# schematic.net
KiCad netlist of a schematic drawn in EAGLE
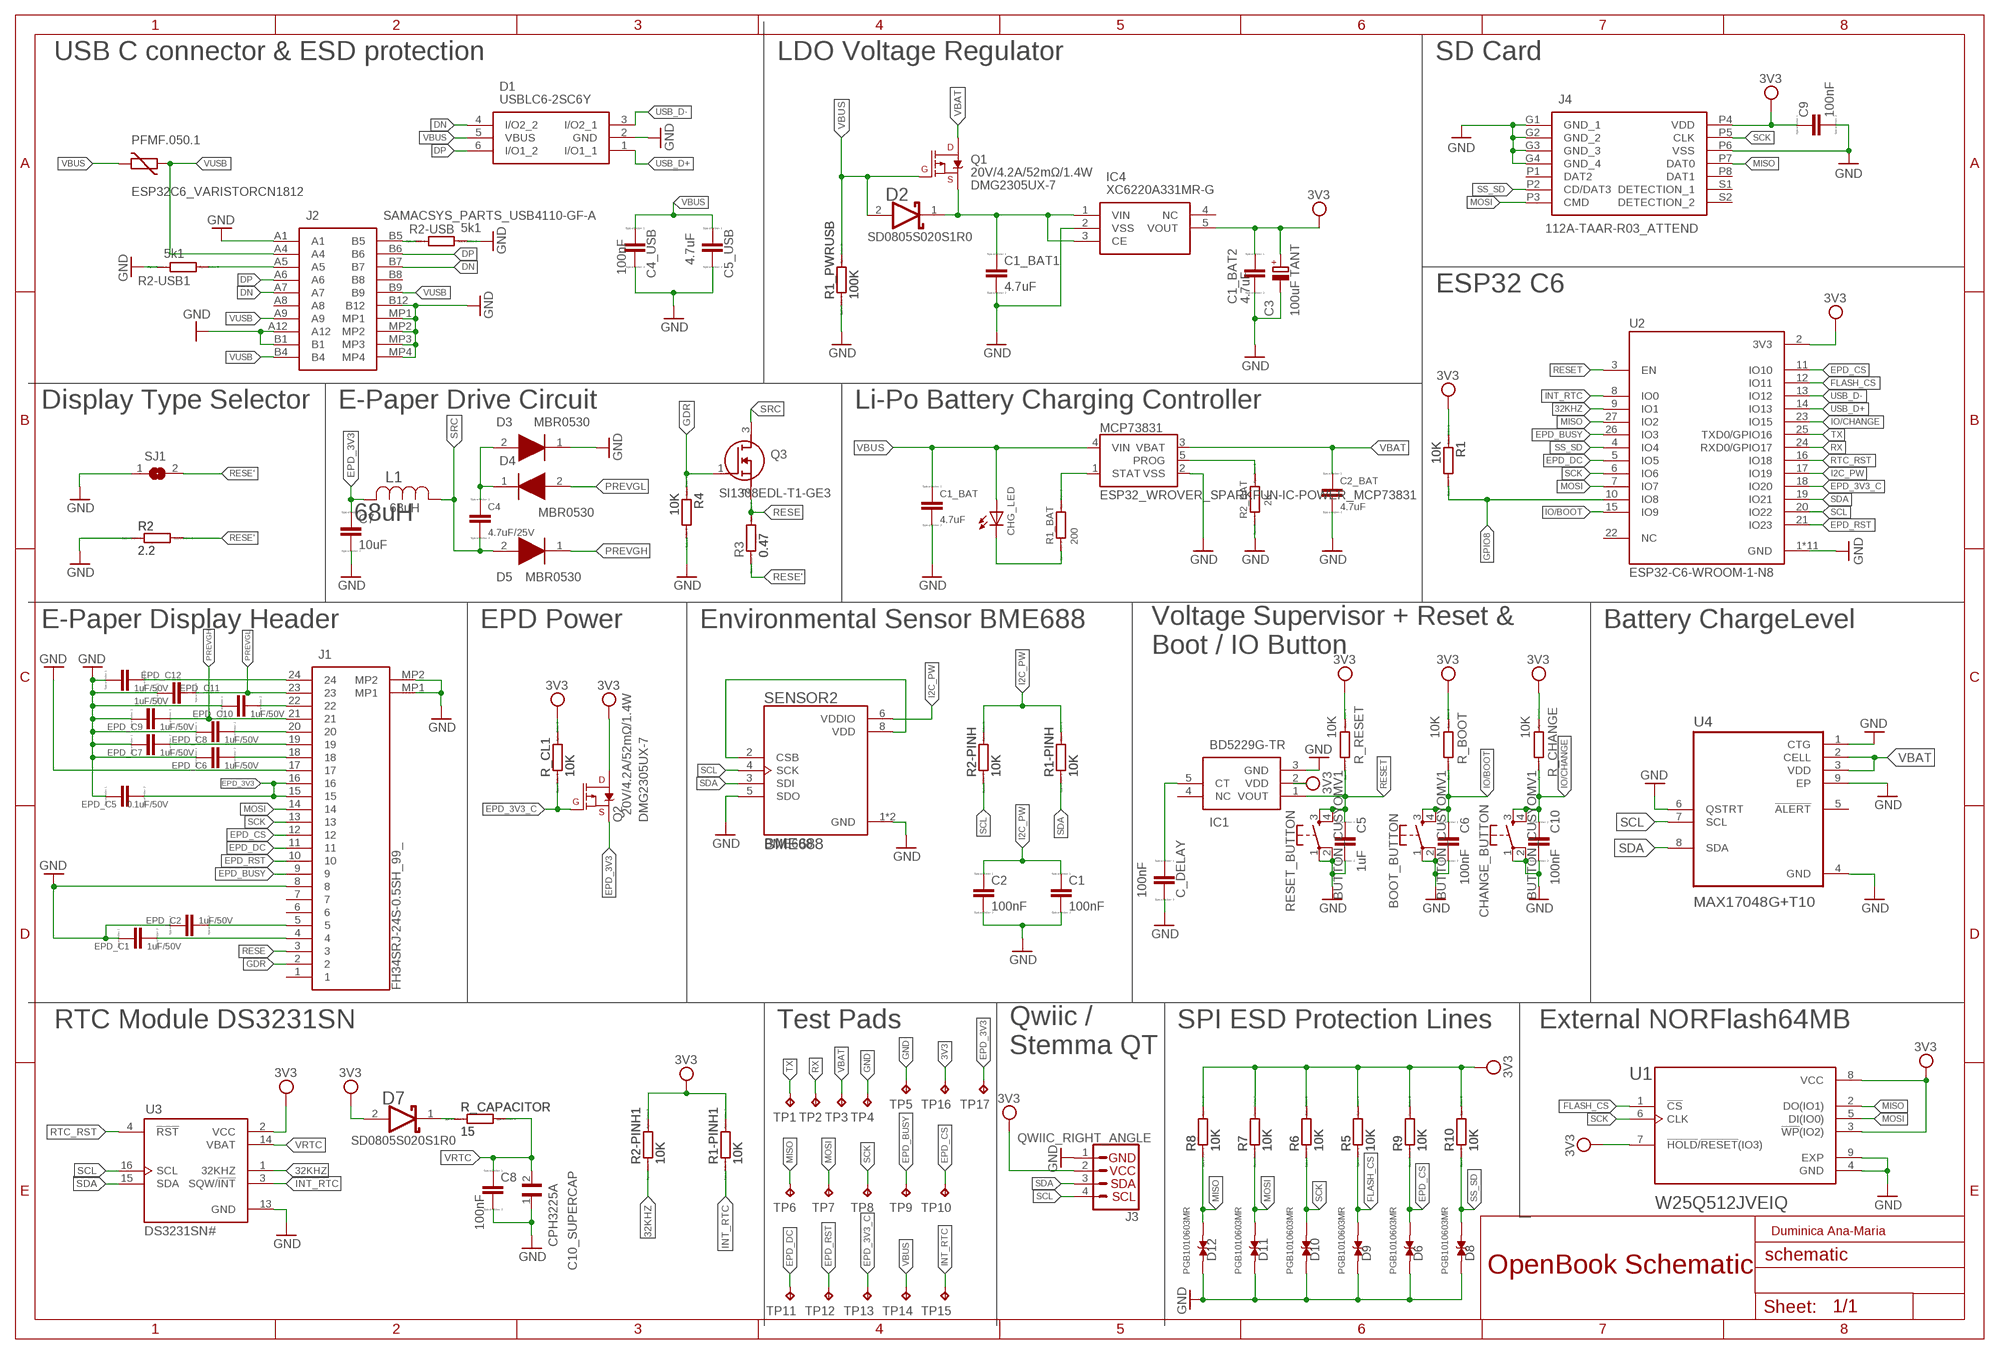
[diagram p0: schematic, sheet 1]

(export (version "E")
  (design (tool "Eeschema 10.0.6"))
  (components
    (comp (ref "BOOT_BUTTON")
      (value "BUTTON_CUSYOMV1")
      (footprint "eagle-import:MYBUTTON")
      (libsource (lib "eagle-import") (part "BUTTON_CUSYOMV1"))
    )
    (comp (ref "C1")
      (value "100nF")
      (footprint "eagle-import:ESP32_WROVER_EAGLE-LTSPICE_C0402")
      (libsource (lib "eagle-import") (part "ESP32_WROVER_EAGLE-LTSPICE_CC0402"))
    )
    (comp (ref "C1_BAT")
      (value "4.7uF")
      (footprint "eagle-import:ESP32_WROVER_EAGLE-LTSPICE_C0402")
      (libsource (lib "eagle-import") (part "ESP32_WROVER_EAGLE-LTSPICE_CC0402"))
    )
    (comp (ref "C1_BAT1")
      (value "4.7uF")
      (footprint "eagle-import:EAGLE-LTSPICE_C0402")
      (libsource (lib "eagle-import") (part "EAGLE-LTSPICE_CC0402"))
    )
    (comp (ref "C1_BAT2")
      (value "4.7uF")
      (footprint "eagle-import:EAGLE-LTSPICE_C0402")
      (libsource (lib "eagle-import") (part "EAGLE-LTSPICE_CC0402"))
    )
    (comp (ref "C2")
      (value "100nF")
      (footprint "eagle-import:ESP32_WROVER_EAGLE-LTSPICE_C0402")
      (libsource (lib "eagle-import") (part "ESP32_WROVER_EAGLE-LTSPICE_CC0402"))
    )
    (comp (ref "C2_BAT")
      (value "4.7uF")
      (footprint "eagle-import:ESP32_WROVER_EAGLE-LTSPICE_C0402")
      (libsource (lib "eagle-import") (part "ESP32_WROVER_EAGLE-LTSPICE_CC0402"))
    )
    (comp (ref "C3")
      (value "100uF TANT")
      (footprint "eagle-import:RCL_CT3528")
      (libsource (lib "eagle-import") (part "RCL_CPOL-EUCT3528"))
    )
    (comp (ref "C4")
      (value "4.7uF/25V")
      (footprint "eagle-import:EAGLE-LTSPICE_C0402")
      (libsource (lib "eagle-import") (part "EAGLE-LTSPICE_CC0402"))
    )
    (comp (ref "C4_USB")
      (value "100nF")
      (footprint "eagle-import:EAGLE-LTSPICE_C0402")
      (libsource (lib "eagle-import") (part "EAGLE-LTSPICE_CC0402"))
    )
    (comp (ref "C5")
      (value "1uF")
      (footprint "eagle-import:ESP32_WROVER_EAGLE-LTSPICE_C0402")
      (libsource (lib "eagle-import") (part "ESP32_WROVER_EAGLE-LTSPICE_CC0402"))
    )
    (comp (ref "C5_USB")
      (value "4.7uF")
      (footprint "eagle-import:EAGLE-LTSPICE_C0402")
      (libsource (lib "eagle-import") (part "EAGLE-LTSPICE_CC0402"))
    )
    (comp (ref "C6")
      (value "100nF")
      (footprint "eagle-import:ESP32_WROVER_EAGLE-LTSPICE_C0402")
      (libsource (lib "eagle-import") (part "ESP32_WROVER_EAGLE-LTSPICE_CC0402"))
    )
    (comp (ref "C7")
      (value "10uF")
      (footprint "eagle-import:EAGLE-LTSPICE_C0402")
      (libsource (lib "eagle-import") (part "EAGLE-LTSPICE_CC0402"))
    )
    (comp (ref "C8")
      (value "100nF")
      (footprint "eagle-import:EAGLE-LTSPICE_C0402")
      (libsource (lib "eagle-import") (part "EAGLE-LTSPICE_CC0402"))
    )
    (comp (ref "C9")
      (value "100nF")
      (footprint "eagle-import:EAGLE-LTSPICE_C0402")
      (libsource (lib "eagle-import") (part "EAGLE-LTSPICE_CC0402"))
    )
    (comp (ref "C10")
      (value "100nF")
      (footprint "eagle-import:ESP32_WROVER_EAGLE-LTSPICE_C0402")
      (libsource (lib "eagle-import") (part "ESP32_WROVER_EAGLE-LTSPICE_CC0402"))
    )
    (comp (ref "C10_SUPERCAP")
      (value "CPH3225A")
      (footprint "eagle-import:CAPCP3225X100N")
      (fields (field (name "MF") "Seiko Instruments"))
      (libsource (lib "eagle-import") (part "CPH3225A"))
    )
    (comp (ref "CHANGE_BUTTON")
      (value "BUTTON_CUSYOMV1")
      (footprint "eagle-import:MYBUTTON")
      (libsource (lib "eagle-import") (part "BUTTON_CUSYOMV1"))
    )
    (comp (ref "CHG_LED")
      (value "ADAFRUIT_LEDCHIP-LED0603")
      (footprint "eagle-import:ADAFRUIT_CHIP-LED0603")
      (libsource (lib "eagle-import") (part "ADAFRUIT_LEDCHIP-LED0603"))
    )
    (comp (ref "C_DELAY")
      (value "100nF")
      (footprint "eagle-import:ESP32_WROVER_EAGLE-LTSPICE_C0402")
      (libsource (lib "eagle-import") (part "ESP32_WROVER_EAGLE-LTSPICE_CC0402"))
    )
    (comp (ref "D1")
      (value "USBLC6-2SC6Y")
      (footprint "eagle-import:SOT95P280X145-6N")
      (fields (field (name "MF") "STMicroelectronics"))
      (libsource (lib "eagle-import") (part "USBLC6-2SC6Y"))
    )
    (comp (ref "D2")
      (value "SD0805S020S1R0")
      (footprint "eagle-import:ESP32_WROVER_AVX---SD0805S020S1R0_AVX_SD0805S020S1R0_0")
      (fields
        (field (name "DIGIKEY_PART_NUMBER") "478-7800-1-ND")
        (field (name "MF") "AVX")
        (field (name "MOUSER_PART_NUMBER") "581-SD0805S020S1R0")
      )
      (libsource (lib "eagle-import") (part "ESP32_WROVER_AVX---SD0805S020S1R0_AVX_SD0805S020S1R0_0_0AVX_SD0805S020S1R0_0_0"))
    )
    (comp (ref "D3")
      (value "MBR0530")
      (footprint "eagle-import:SOD3716X135N")
      (fields (field (name "MF") "ON Semiconductor"))
      (libsource (lib "eagle-import") (part "MBR0530"))
    )
    (comp (ref "D4")
      (value "MBR0530")
      (footprint "eagle-import:SOD3716X135N")
      (fields (field (name "MF") "ON Semiconductor"))
      (libsource (lib "eagle-import") (part "MBR0530"))
    )
    (comp (ref "D5")
      (value "MBR0530")
      (footprint "eagle-import:SOD3716X135N")
      (fields (field (name "MF") "ON Semiconductor"))
      (libsource (lib "eagle-import") (part "MBR0530"))
    )
    (comp (ref "D6")
      (value "PGB1010603MR")
      (footprint "eagle-import:DIOC1608X36N")
      (fields (field (name "MF") "Littelfuse Inc."))
      (libsource (lib "eagle-import") (part "PGB1010603MR"))
    )
    (comp (ref "D7")
      (value "SD0805S020S1R0")
      (footprint "eagle-import:ESP32_WROVER_AVX---SD0805S020S1R0_AVX_SD0805S020S1R0_0")
      (fields
        (field (name "DIGIKEY_PART_NUMBER") "478-7800-1-ND")
        (field (name "MF") "AVX")
        (field (name "MOUSER_PART_NUMBER") "581-SD0805S020S1R0")
      )
      (libsource (lib "eagle-import") (part "ESP32_WROVER_AVX---SD0805S020S1R0_AVX_SD0805S020S1R0_0_0AVX_SD0805S020S1R0_0_0"))
    )
    (comp (ref "D8")
      (value "PGB1010603MR")
      (footprint "eagle-import:DIOC1608X36N")
      (fields (field (name "MF") "Littelfuse Inc."))
      (libsource (lib "eagle-import") (part "PGB1010603MR"))
    )
    (comp (ref "D9")
      (value "PGB1010603MR")
      (footprint "eagle-import:DIOC1608X36N")
      (fields (field (name "MF") "Littelfuse Inc."))
      (libsource (lib "eagle-import") (part "PGB1010603MR"))
    )
    (comp (ref "D10")
      (value "PGB1010603MR")
      (footprint "eagle-import:DIOC1608X36N")
      (fields (field (name "MF") "Littelfuse Inc."))
      (libsource (lib "eagle-import") (part "PGB1010603MR"))
    )
    (comp (ref "D11")
      (value "PGB1010603MR")
      (footprint "eagle-import:DIOC1608X36N")
      (fields (field (name "MF") "Littelfuse Inc."))
      (libsource (lib "eagle-import") (part "PGB1010603MR"))
    )
    (comp (ref "D12")
      (value "PGB1010603MR")
      (footprint "eagle-import:DIOC1608X36N")
      (fields (field (name "MF") "Littelfuse Inc."))
      (libsource (lib "eagle-import") (part "PGB1010603MR"))
    )
    (comp (ref "EPD_C1")
      (value "1uF/50V")
      (footprint "eagle-import:ESP32_WROVER_EAGLE-LTSPICE_C0402")
      (libsource (lib "eagle-import") (part "ESP32_WROVER_EAGLE-LTSPICE_CC0402"))
    )
    (comp (ref "EPD_C2")
      (value "1uF/50V")
      (footprint "eagle-import:ESP32_WROVER_EAGLE-LTSPICE_C0402")
      (libsource (lib "eagle-import") (part "ESP32_WROVER_EAGLE-LTSPICE_CC0402"))
    )
    (comp (ref "EPD_C5")
      (value "0.1uF/50V")
      (footprint "eagle-import:ESP32_WROVER_EAGLE-LTSPICE_C0402")
      (libsource (lib "eagle-import") (part "ESP32_WROVER_EAGLE-LTSPICE_CC0402"))
    )
    (comp (ref "EPD_C6")
      (value "1uF/50V")
      (footprint "eagle-import:ESP32_WROVER_EAGLE-LTSPICE_C0402")
      (libsource (lib "eagle-import") (part "ESP32_WROVER_EAGLE-LTSPICE_CC0402"))
    )
    (comp (ref "EPD_C7")
      (value "1uF/50V")
      (footprint "eagle-import:ESP32_WROVER_EAGLE-LTSPICE_C0402")
      (libsource (lib "eagle-import") (part "ESP32_WROVER_EAGLE-LTSPICE_CC0402"))
    )
    (comp (ref "EPD_C8")
      (value "1uF/50V")
      (footprint "eagle-import:ESP32_WROVER_EAGLE-LTSPICE_C0402")
      (libsource (lib "eagle-import") (part "ESP32_WROVER_EAGLE-LTSPICE_CC0402"))
    )
    (comp (ref "EPD_C9")
      (value "1uF/50V")
      (footprint "eagle-import:ESP32_WROVER_EAGLE-LTSPICE_C0402")
      (libsource (lib "eagle-import") (part "ESP32_WROVER_EAGLE-LTSPICE_CC0402"))
    )
    (comp (ref "EPD_C10")
      (value "1uF/50V")
      (footprint "eagle-import:ESP32_WROVER_EAGLE-LTSPICE_C0402")
      (libsource (lib "eagle-import") (part "ESP32_WROVER_EAGLE-LTSPICE_CC0402"))
    )
    (comp (ref "EPD_C11")
      (value "1uF/50V")
      (footprint "eagle-import:ESP32_WROVER_EAGLE-LTSPICE_C0402")
      (libsource (lib "eagle-import") (part "ESP32_WROVER_EAGLE-LTSPICE_CC0402"))
    )
    (comp (ref "EPD_C12")
      (value "1uF/50V")
      (footprint "eagle-import:ESP32_WROVER_EAGLE-LTSPICE_C0402")
      (libsource (lib "eagle-import") (part "ESP32_WROVER_EAGLE-LTSPICE_CC0402"))
    )
    (comp (ref "IC1")
      (value "BD5229G-TR")
      (footprint "eagle-import:SOT95P280X125-5N")
      (fields (field (name "MOUSER_PART_NUMBER") "755-BD5229G-TR"))
      (libsource (lib "eagle-import") (part "BD5229G-TR"))
    )
    (comp (ref "IC4")
      (value "XC6220A331MR-G")
      (footprint "eagle-import:SOT95P280X120-5N")
      (fields (field (name "MOUSER_PART_NUMBER") "865-XC6220A331MR-G"))
      (libsource (lib "eagle-import") (part "XC6220A331MR-G"))
    )
    (comp (ref "J1")
      (value "FH34SRJ-24S-0.5SH_99_")
      (footprint "eagle-import:FH34SRJ24S05SH99")
      (fields
        (field (name "MANUFACTURER_PART_NUMBER") "FH34SRJ-24S-0.5SH(99)")
        (field (name "MOUSER_PART_NUMBER") "798-FH34SRJ24S05SH99")
      )
      (libsource (lib "eagle-import") (part "FH34SRJ-24S-0.5SH_99_"))
    )
    (comp (ref "J2")
      (value "SAMACSYS_PARTS_USB4110-GF-A")
      (footprint "eagle-import:SAMACSYS_PARTS_USB4110GFA")
      (fields
        (field (name "MANUFACTURER_PART_NUMBER") "USB4110-GF-A")
        (field (name "MOUSER_PART_NUMBER") "640-USB4110-GF-A")
      )
      (libsource (lib "eagle-import") (part "SAMACSYS_PARTS_USB4110-GF-A"))
    )
    (comp (ref "J3")
      (value "QWIIC_RIGHT_ANGLE")
      (footprint "eagle-import:JST04_1MM_RA")
      (libsource (lib "eagle-import") (part "QWIIC_CONNECTORJS-1MM"))
    )
    (comp (ref "J4")
      (value "112A-TAAR-R03_ATTEND")
      (footprint "eagle-import:112ATAARR03ATTEND")
      (fields (field (name "MANUFACTURER_PART_NUMBER") "112A-TAAR-R03 ATTEND"))
      (libsource (lib "eagle-import") (part "112A-TAAR-R03_ATTEND"))
    )
    (comp (ref "L1")
      (value "68uH")
      (footprint "eagle-import:IND_4828-WE-TPC_WRE")
      (fields
        (field (name "MANUFACTURER_PART_NUMBER") "744043680")
        (field (name "COPYRIGHT") "Copyright (C) 2024 Ultra Librarian. All rights reserved.")
      )
      (libsource (lib "eagle-import") (part "744043680IND_4828-WE-TPC_WRE"))
    )
    (comp (ref "MCP73831")
      (value "ESP32_WROVER_SPARKFUN-IC-POWER_MCP73831")
      (footprint "eagle-import:ESP32_WROVER_SPARKFUN-IC-POWER_SOT23-5")
      (libsource (lib "eagle-import") (part "ESP32_WROVER_SPARKFUN-IC-POWER_MCP73831"))
    )
    (comp (ref "PFMF.050.1")
      (value "ESP32C6_VARISTORCN1812")
      (footprint "eagle-import:ESP32C6_VARISTOR_CT_CN1812")
      (libsource (lib "eagle-import") (part "ESP32C6_VARISTORCN1812"))
    )
    (comp (ref "Q1")
      (value "20V/4.2A/52mΩ/1.4W")
      (footprint "eagle-import:ESP32_WROVER_SPARKFUN-DISCRETESEMI_SOT23-3")
      (libsource (lib "eagle-import") (part "ESP32_WROVER_SPARKFUN-DISCRETESEMI_MOSFET_PCH-DMG2305UX-7"))
    )
    (comp (ref "Q2")
      (value "20V/4.2A/52mΩ/1.4W")
      (footprint "eagle-import:ESP32_WROVER_SPARKFUN-DISCRETESEMI_SOT23-3")
      (libsource (lib "eagle-import") (part "ESP32_WROVER_SPARKFUN-DISCRETESEMI_MOSFET_PCH-DMG2305UX-7"))
    )
    (comp (ref "Q3")
      (value "SI1308EDL-T1-GE3")
      (footprint "eagle-import:SOT65P210X110-3N")
      (fields (field (name "MF") "Vishay Siliconix"))
      (libsource (lib "eagle-import") (part "SI1308EDL-T1-GE3"))
    )
    (comp (ref "R1")
      (value "10K")
      (footprint "eagle-import:ESP32_WROVER_EAGLE-LTSPICE_R0402")
      (libsource (lib "eagle-import") (part "ESP32_WROVER_EAGLE-LTSPICE_RR0402"))
    )
    (comp (ref "R1-PINH")
      (value "10K")
      (footprint "eagle-import:ESP32_WROVER_EAGLE-LTSPICE_R0402")
      (libsource (lib "eagle-import") (part "ESP32_WROVER_EAGLE-LTSPICE_RR0402"))
    )
    (comp (ref "R1-PINH1")
      (value "10K")
      (footprint "eagle-import:ESP32_WROVER_EAGLE-LTSPICE_R0402")
      (libsource (lib "eagle-import") (part "ESP32_WROVER_EAGLE-LTSPICE_RR0402"))
    )
    (comp (ref "R1_BAT")
      (value "200")
      (footprint "eagle-import:ESP32_WROVER_EAGLE-LTSPICE_R0402")
      (libsource (lib "eagle-import") (part "ESP32_WROVER_EAGLE-LTSPICE_RR0402"))
    )
    (comp (ref "R1_PWRUSB")
      (value "100K")
      (footprint "eagle-import:ESP32_WROVER_EAGLE-LTSPICE_R0402")
      (libsource (lib "eagle-import") (part "ESP32_WROVER_EAGLE-LTSPICE_RR0402"))
    )
    (comp (ref "R2")
      (value "2.2")
      (footprint "eagle-import:ESP32_WROVER_EAGLE-LTSPICE_R0402")
      (libsource (lib "eagle-import") (part "ESP32_WROVER_EAGLE-LTSPICE_RR0402"))
    )
    (comp (ref "R2-PINH")
      (value "10K")
      (footprint "eagle-import:ESP32_WROVER_EAGLE-LTSPICE_R0402")
      (libsource (lib "eagle-import") (part "ESP32_WROVER_EAGLE-LTSPICE_RR0402"))
    )
    (comp (ref "R2-PINH1")
      (value "10K")
      (footprint "eagle-import:ESP32_WROVER_EAGLE-LTSPICE_R0402")
      (libsource (lib "eagle-import") (part "ESP32_WROVER_EAGLE-LTSPICE_RR0402"))
    )
    (comp (ref "R2-USB")
      (value "5k1")
      (footprint "eagle-import:ESP32_WROVER_EAGLE-LTSPICE_R0402")
      (libsource (lib "eagle-import") (part "ESP32_WROVER_EAGLE-LTSPICE_RR0402"))
    )
    (comp (ref "R2-USB1")
      (value "5k1")
      (footprint "eagle-import:ESP32_WROVER_EAGLE-LTSPICE_R0402")
      (libsource (lib "eagle-import") (part "ESP32_WROVER_EAGLE-LTSPICE_RR0402"))
    )
    (comp (ref "R2_BAT")
      (value "2K")
      (footprint "eagle-import:ESP32_WROVER_EAGLE-LTSPICE_R0402")
      (libsource (lib "eagle-import") (part "ESP32_WROVER_EAGLE-LTSPICE_RR0402"))
    )
    (comp (ref "R3")
      (value "0.47")
      (footprint "eagle-import:ESP32_WROVER_EAGLE-LTSPICE_R0402")
      (libsource (lib "eagle-import") (part "ESP32_WROVER_EAGLE-LTSPICE_RR0402"))
    )
    (comp (ref "R4")
      (value "10K")
      (footprint "eagle-import:ESP32_WROVER_EAGLE-LTSPICE_R0402")
      (libsource (lib "eagle-import") (part "ESP32_WROVER_EAGLE-LTSPICE_RR0402"))
    )
    (comp (ref "R5")
      (value "10K")
      (footprint "eagle-import:ESP32_WROVER_EAGLE-LTSPICE_R0402")
      (libsource (lib "eagle-import") (part "ESP32_WROVER_EAGLE-LTSPICE_RR0402"))
    )
    (comp (ref "R6")
      (value "10K")
      (footprint "eagle-import:ESP32_WROVER_EAGLE-LTSPICE_R0402")
      (libsource (lib "eagle-import") (part "ESP32_WROVER_EAGLE-LTSPICE_RR0402"))
    )
    (comp (ref "R7")
      (value "10K")
      (footprint "eagle-import:ESP32_WROVER_EAGLE-LTSPICE_R0402")
      (libsource (lib "eagle-import") (part "ESP32_WROVER_EAGLE-LTSPICE_RR0402"))
    )
    (comp (ref "R8")
      (value "10K")
      (footprint "eagle-import:ESP32_WROVER_EAGLE-LTSPICE_R0402")
      (libsource (lib "eagle-import") (part "ESP32_WROVER_EAGLE-LTSPICE_RR0402"))
    )
    (comp (ref "R9")
      (value "10K")
      (footprint "eagle-import:ESP32_WROVER_EAGLE-LTSPICE_R0402")
      (libsource (lib "eagle-import") (part "ESP32_WROVER_EAGLE-LTSPICE_RR0402"))
    )
    (comp (ref "R10")
      (value "10K")
      (footprint "eagle-import:ESP32_WROVER_EAGLE-LTSPICE_R0402")
      (libsource (lib "eagle-import") (part "ESP32_WROVER_EAGLE-LTSPICE_RR0402"))
    )
    (comp (ref "RESET_BUTTON")
      (value "BUTTON_CUSYOMV1")
      (footprint "eagle-import:MYBUTTON")
      (libsource (lib "eagle-import") (part "BUTTON_CUSYOMV1"))
    )
    (comp (ref "R_BOOT")
      (value "10K")
      (footprint "eagle-import:ESP32_WROVER_EAGLE-LTSPICE_R0402")
      (libsource (lib "eagle-import") (part "ESP32_WROVER_EAGLE-LTSPICE_RR0402"))
    )
    (comp (ref "R_CAPACITOR")
      (value "15")
      (footprint "eagle-import:ESP32_WROVER_EAGLE-LTSPICE_R0402")
      (libsource (lib "eagle-import") (part "ESP32_WROVER_EAGLE-LTSPICE_RR0402"))
    )
    (comp (ref "R_CHANGE")
      (value "10K")
      (footprint "eagle-import:ESP32_WROVER_EAGLE-LTSPICE_R0402")
      (libsource (lib "eagle-import") (part "ESP32_WROVER_EAGLE-LTSPICE_RR0402"))
    )
    (comp (ref "R_CL1")
      (value "10K")
      (footprint "eagle-import:ESP32_WROVER_EAGLE-LTSPICE_R0402")
      (libsource (lib "eagle-import") (part "ESP32_WROVER_EAGLE-LTSPICE_RR0402"))
    )
    (comp (ref "R_RESET")
      (value "10K")
      (footprint "eagle-import:ESP32_WROVER_EAGLE-LTSPICE_R0402")
      (libsource (lib "eagle-import") (part "ESP32_WROVER_EAGLE-LTSPICE_RR0402"))
    )
    (comp (ref "SENSOR2")
      (value "BME688")
      (footprint "eagle-import:ESP32_WROVER_BME680_PSON80P300X300X100-8N")
      (fields (field (name "MF") "Bosch Sensortec") (field (name "MP") "BME680"))
      (libsource (lib "eagle-import") (part "ESP32_WROVER_BME680_BME680"))
    )
    (comp (ref "SJ1") (value "SJ") (footprint "eagle-import:SJ") (libsource (lib "eagle-import") (part "SJ")))
    (comp (ref "TP1")
      (value "TPTP20R")
      (footprint "eagle-import:TP20R")
      (libsource (lib "eagle-import") (part "TPTP20R"))
    )
    (comp (ref "TP2")
      (value "TPTP20R")
      (footprint "eagle-import:TP20R")
      (libsource (lib "eagle-import") (part "TPTP20R"))
    )
    (comp (ref "TP3")
      (value "TPTP20R")
      (footprint "eagle-import:TP20R")
      (libsource (lib "eagle-import") (part "TPTP20R"))
    )
    (comp (ref "TP4")
      (value "TPTP20R")
      (footprint "eagle-import:TP20R")
      (libsource (lib "eagle-import") (part "TPTP20R"))
    )
    (comp (ref "TP5")
      (value "TPTP20R")
      (footprint "eagle-import:TP20R")
      (libsource (lib "eagle-import") (part "TPTP20R"))
    )
    (comp (ref "TP6")
      (value "TPTP20R")
      (footprint "eagle-import:TP20R")
      (libsource (lib "eagle-import") (part "TPTP20R"))
    )
    (comp (ref "TP7")
      (value "TPTP20R")
      (footprint "eagle-import:TP20R")
      (libsource (lib "eagle-import") (part "TPTP20R"))
    )
    (comp (ref "TP8")
      (value "TPTP20R")
      (footprint "eagle-import:TP20R")
      (libsource (lib "eagle-import") (part "TPTP20R"))
    )
    (comp (ref "TP9")
      (value "TPTP20R")
      (footprint "eagle-import:TP20R")
      (libsource (lib "eagle-import") (part "TPTP20R"))
    )
    (comp (ref "TP10")
      (value "TPTP20R")
      (footprint "eagle-import:TP20R")
      (libsource (lib "eagle-import") (part "TPTP20R"))
    )
    (comp (ref "TP11")
      (value "TPTP20R")
      (footprint "eagle-import:TP20R")
      (libsource (lib "eagle-import") (part "TPTP20R"))
    )
    (comp (ref "TP12")
      (value "TPTP20R")
      (footprint "eagle-import:TP20R")
      (libsource (lib "eagle-import") (part "TPTP20R"))
    )
    (comp (ref "TP13")
      (value "TPTP20R")
      (footprint "eagle-import:TP20R")
      (libsource (lib "eagle-import") (part "TPTP20R"))
    )
    (comp (ref "TP14")
      (value "TPTP20R")
      (footprint "eagle-import:TP20R")
      (libsource (lib "eagle-import") (part "TPTP20R"))
    )
    (comp (ref "TP15")
      (value "TPTP20R")
      (footprint "eagle-import:TP20R")
      (libsource (lib "eagle-import") (part "TPTP20R"))
    )
    (comp (ref "TP16")
      (value "TPTP20R")
      (footprint "eagle-import:TP20R")
      (libsource (lib "eagle-import") (part "TPTP20R"))
    )
    (comp (ref "TP17")
      (value "TPTP20R")
      (footprint "eagle-import:TP20R")
      (libsource (lib "eagle-import") (part "TPTP20R"))
    )
    (comp (ref "U1")
      (value "W25Q512JVEIQ")
      (footprint "eagle-import:SON127P600X800X80-9N")
      (fields (field (name "MF") "Winbond Electronics"))
      (libsource (lib "eagle-import") (part "W25Q512JVEIQ"))
    )
    (comp (ref "U2")
      (value "ESP32-C6-WROOM-1-N8")
      (footprint "eagle-import:XCVR_ESP32-C6-WROOM-1-N8")
      (fields (field (name "MF") "Espressif Systems"))
      (libsource (lib "eagle-import") (part "ESP32-C6-WROOM-1-N8"))
    )
    (comp (ref "U3")
      (value "DS3231SN#")
      (footprint "eagle-import:SOIC127P1032X265-16N")
      (fields (field (name "MF") "Analog Devices"))
      (libsource (lib "eagle-import") (part "DS3231SN#"))
    )
    (comp (ref "U4")
      (value "MAX17048G+T10")
      (footprint "eagle-import:SON50P200X200X80-9N")
      (fields (field (name "MF") "Analog Devices"))
      (libsource (lib "eagle-import") (part "MAX17048G+T10"))
    )
  )
  (nets
    (net (code "1") (name "3V3") (class "Default")
      (node (ref "C1_BAT2") (pin "1") (pinfunction "1_1") (pintype "passive"))
      (node (ref "C3") (pin "+") (pinfunction "+_+") (pintype "passive"))
      (node (ref "C9") (pin "1") (pinfunction "1_1") (pintype "passive"))
      (node (ref "D7") (pin "2") (pinfunction "ANODE_2") (pintype "bidirectional"))
      (node (ref "IC1") (pin "2") (pinfunction "VDD_2") (pintype "bidirectional"))
      (node (ref "IC4") (pin "5") (pinfunction "VOUT_5") (pintype "bidirectional"))
      (node (ref "J3") (pin "2") (pinfunction "2_2") (pintype "passive"))
      (node (ref "J4") (pin "P4") (pinfunction "VDD_P4") (pintype "bidirectional"))
      (node (ref "Q2") (pin "3") (pinfunction "D_3") (pintype "bidirectional"))
      (node (ref "R1") (pin "1") (pinfunction "1_1") (pintype "passive"))
      (node (ref "R1-PINH1") (pin "2") (pinfunction "2_2") (pintype "passive"))
      (node (ref "R10") (pin "2") (pinfunction "2_2") (pintype "passive"))
      (node (ref "R2-PINH1") (pin "2") (pinfunction "2_2") (pintype "passive"))
      (node (ref "R5") (pin "2") (pinfunction "2_2") (pintype "passive"))
      (node (ref "R6") (pin "2") (pinfunction "2_2") (pintype "passive"))
      (node (ref "R7") (pin "2") (pinfunction "2_2") (pintype "passive"))
      (node (ref "R8") (pin "2") (pinfunction "2_2") (pintype "passive"))
      (node (ref "R9") (pin "2") (pinfunction "2_2") (pintype "passive"))
      (node (ref "R_BOOT") (pin "2") (pinfunction "2_2") (pintype "passive"))
      (node (ref "R_CHANGE") (pin "2") (pinfunction "2_2") (pintype "passive"))
      (node (ref "R_CL1") (pin "2") (pinfunction "2_2") (pintype "passive"))
      (node (ref "R_RESET") (pin "2") (pinfunction "2_2") (pintype "passive"))
      (node (ref "TP16") (pin "TP") (pinfunction "TP_TP") (pintype "input"))
      (node (ref "U1") (pin "3") (pinfunction "~{WP}(IO2)_3") (pintype "bidirectional"))
      (node (ref "U1") (pin "7") (pinfunction "~{HOLD}/~{RESET}(IO3)_7") (pintype "bidirectional"))
      (node (ref "U1") (pin "8") (pinfunction "VCC_8") (pintype "power_in"))
      (node (ref "U2") (pin "2") (pinfunction "3V3_2") (pintype "power_in"))
      (node (ref "U3") (pin "2") (pinfunction "VCC_2") (pintype "power_in"))
    )
    (net (code "2") (name "32KHZ") (class "Default")
      (node (ref "R2-PINH1") (pin "1") (pinfunction "1_1") (pintype "passive"))
      (node (ref "U2") (pin "9") (pinfunction "IO1_9") (pintype "bidirectional"))
      (node (ref "U3") (pin "1") (pinfunction "32KHZ_1") (pintype "output"))
    )
    (net (code "3") (name "DN") (class "Default")
      (node (ref "D1") (pin "4") (pinfunction "I/O2_2_4") (pintype "bidirectional"))
      (node (ref "J2") (pin "A7") (pinfunction "A7_A7") (pintype "bidirectional"))
      (node (ref "J2") (pin "B7") (pinfunction "B7_B7") (pintype "bidirectional"))
    )
    (net (code "4") (name "DP") (class "Default")
      (node (ref "D1") (pin "6") (pinfunction "I/O1_2_6") (pintype "bidirectional"))
      (node (ref "J2") (pin "A6") (pinfunction "A6_A6") (pintype "bidirectional"))
      (node (ref "J2") (pin "B6") (pinfunction "B6_B6") (pintype "bidirectional"))
    )
    (net (code "5") (name "EPD_3V3") (class "Default")
      (node (ref "C7") (pin "1") (pinfunction "1_1") (pintype "passive"))
      (node (ref "EPD_C5") (pin "2") (pinfunction "2_2") (pintype "passive"))
      (node (ref "J1") (pin "15") (pinfunction "15_15") (pintype "bidirectional"))
      (node (ref "J1") (pin "16") (pinfunction "16_16") (pintype "bidirectional"))
      (node (ref "L1") (pin "2") (pinfunction "2_2") (pintype "passive"))
      (node (ref "Q2") (pin "2") (pinfunction "S_2") (pintype "bidirectional"))
      (node (ref "TP17") (pin "TP") (pinfunction "TP_TP") (pintype "input"))
    )
    (net (code "6") (name "EPD_3V3_C") (class "Default")
      (node (ref "Q2") (pin "1") (pinfunction "G_1") (pintype "bidirectional"))
      (node (ref "R_CL1") (pin "1") (pinfunction "1_1") (pintype "passive"))
      (node (ref "TP13") (pin "TP") (pinfunction "TP_TP") (pintype "input"))
      (node (ref "U2") (pin "18") (pinfunction "IO20_18") (pintype "bidirectional"))
    )
    (net (code "7") (name "EPD_BUSY") (class "Default")
      (node (ref "J1") (pin "9") (pinfunction "9_9") (pintype "bidirectional"))
      (node (ref "TP9") (pin "TP") (pinfunction "TP_TP") (pintype "input"))
      (node (ref "U2") (pin "26") (pinfunction "IO3_26") (pintype "bidirectional"))
    )
    (net (code "8") (name "EPD_CS") (class "Default")
      (node (ref "D6") (pin "2") (pinfunction "2_2") (pintype "passive"))
      (node (ref "J1") (pin "12") (pinfunction "12_12") (pintype "bidirectional"))
      (node (ref "R9") (pin "1") (pinfunction "1_1") (pintype "passive"))
      (node (ref "TP10") (pin "TP") (pinfunction "TP_TP") (pintype "input"))
      (node (ref "U2") (pin "11") (pinfunction "IO10_11") (pintype "bidirectional"))
    )
    (net (code "9") (name "EPD_DC") (class "Default")
      (node (ref "J1") (pin "11") (pinfunction "11_11") (pintype "bidirectional"))
      (node (ref "TP11") (pin "TP") (pinfunction "TP_TP") (pintype "input"))
      (node (ref "U2") (pin "5") (pinfunction "IO5_5") (pintype "bidirectional"))
    )
    (net (code "10") (name "EPD_RST") (class "Default")
      (node (ref "J1") (pin "10") (pinfunction "10_10") (pintype "bidirectional"))
      (node (ref "TP12") (pin "TP") (pinfunction "TP_TP") (pintype "input"))
      (node (ref "U2") (pin "21") (pinfunction "IO23_21") (pintype "bidirectional"))
    )
    (net (code "11") (name "FLASH_CS") (class "Default")
      (node (ref "D9") (pin "2") (pinfunction "2_2") (pintype "passive"))
      (node (ref "R5") (pin "1") (pinfunction "1_1") (pintype "passive"))
      (node (ref "U1") (pin "1") (pinfunction "~{CS}_1") (pintype "input"))
      (node (ref "U2") (pin "12") (pinfunction "IO11_12") (pintype "bidirectional"))
    )
    (net (code "12") (name "GDR") (class "Default")
      (node (ref "J1") (pin "2") (pinfunction "2_2") (pintype "bidirectional"))
      (node (ref "Q3") (pin "1") (pinfunction "G_1") (pintype "bidirectional"))
      (node (ref "R4") (pin "1") (pinfunction "1_1") (pintype "passive"))
    )
    (net (code "13") (name "GND") (class "Default")
      (node (ref "BOOT_BUTTON") (pin "1") (pinfunction "1_1") (pintype "passive"))
      (node (ref "BOOT_BUTTON") (pin "2") (pinfunction "2_2") (pintype "passive"))
      (node (ref "C1") (pin "2") (pinfunction "2_2") (pintype "passive"))
      (node (ref "C10") (pin "2") (pinfunction "2_2") (pintype "passive"))
      (node (ref "C10_SUPERCAP") (pin "1") (pinfunction "1_1") (pintype "passive"))
      (node (ref "C1_BAT") (pin "2") (pinfunction "2_2") (pintype "passive"))
      (node (ref "C1_BAT1") (pin "2") (pinfunction "2_2") (pintype "passive"))
      (node (ref "C1_BAT2") (pin "2") (pinfunction "2_2") (pintype "passive"))
      (node (ref "C2") (pin "2") (pinfunction "2_2") (pintype "passive"))
      (node (ref "C2_BAT") (pin "2") (pinfunction "2_2") (pintype "passive"))
      (node (ref "C3") (pin "-") (pinfunction "-_-") (pintype "passive"))
      (node (ref "C4_USB") (pin "2") (pinfunction "2_2") (pintype "passive"))
      (node (ref "C5") (pin "2") (pinfunction "2_2") (pintype "passive"))
      (node (ref "C5_USB") (pin "2") (pinfunction "2_2") (pintype "passive"))
      (node (ref "C6") (pin "2") (pinfunction "2_2") (pintype "passive"))
      (node (ref "C7") (pin "2") (pinfunction "2_2") (pintype "passive"))
      (node (ref "C8") (pin "2") (pinfunction "2_2") (pintype "passive"))
      (node (ref "C9") (pin "2") (pinfunction "2_2") (pintype "passive"))
      (node (ref "CHANGE_BUTTON") (pin "1") (pinfunction "1_1") (pintype "passive"))
      (node (ref "CHANGE_BUTTON") (pin "2") (pinfunction "2_2") (pintype "passive"))
      (node (ref "C_DELAY") (pin "2") (pinfunction "2_2") (pintype "passive"))
      (node (ref "D1") (pin "2") (pinfunction "GND_2") (pintype "bidirectional"))
      (node (ref "D10") (pin "1") (pinfunction "1_1") (pintype "passive"))
      (node (ref "D11") (pin "1") (pinfunction "1_1") (pintype "passive"))
      (node (ref "D12") (pin "1") (pinfunction "1_1") (pintype "passive"))
      (node (ref "D3") (pin "1") (pinfunction "K_1") (pintype "bidirectional"))
      (node (ref "D6") (pin "1") (pinfunction "1_1") (pintype "passive"))
      (node (ref "D8") (pin "1") (pinfunction "1_1") (pintype "passive"))
      (node (ref "D9") (pin "1") (pinfunction "1_1") (pintype "passive"))
      (node (ref "EPD_C1") (pin "1") (pinfunction "1_1") (pintype "passive"))
      (node (ref "EPD_C10") (pin "1") (pinfunction "1_1") (pintype "passive"))
      (node (ref "EPD_C11") (pin "1") (pinfunction "1_1") (pintype "passive"))
      (node (ref "EPD_C12") (pin "1") (pinfunction "1_1") (pintype "passive"))
      (node (ref "EPD_C2") (pin "1") (pinfunction "1_1") (pintype "passive"))
      (node (ref "EPD_C5") (pin "1") (pinfunction "1_1") (pintype "passive"))
      (node (ref "EPD_C6") (pin "1") (pinfunction "1_1") (pintype "passive"))
      (node (ref "EPD_C7") (pin "1") (pinfunction "1_1") (pintype "passive"))
      (node (ref "EPD_C8") (pin "1") (pinfunction "1_1") (pintype "passive"))
      (node (ref "EPD_C9") (pin "1") (pinfunction "1_1") (pintype "passive"))
      (node (ref "IC1") (pin "3") (pinfunction "GND_3") (pintype "bidirectional"))
      (node (ref "IC4") (pin "2") (pinfunction "VSS_2") (pintype "bidirectional"))
      (node (ref "J1") (pin "17") (pinfunction "17_17") (pintype "bidirectional"))
      (node (ref "J1") (pin "8") (pinfunction "8_8") (pintype "bidirectional"))
      (node (ref "J1") (pin "MP1") (pinfunction "MP1_MP1") (pintype "bidirectional"))
      (node (ref "J1") (pin "MP2") (pinfunction "MP2_MP2") (pintype "bidirectional"))
      (node (ref "J2") (pin "A1") (pinfunction "A1_A1") (pintype "bidirectional"))
      (node (ref "J2") (pin "A12") (pinfunction "A12_A12") (pintype "bidirectional"))
      (node (ref "J2") (pin "B1") (pinfunction "B1_B1") (pintype "bidirectional"))
      (node (ref "J2") (pin "B12") (pinfunction "B12_B12") (pintype "bidirectional"))
      (node (ref "J2") (pin "MP1") (pinfunction "MP1_MP1") (pintype "bidirectional"))
      (node (ref "J2") (pin "MP2") (pinfunction "MP2_MP2") (pintype "bidirectional"))
      (node (ref "J2") (pin "MP3") (pinfunction "MP3_MP3") (pintype "bidirectional"))
      (node (ref "J2") (pin "MP4") (pinfunction "MP4_MP4") (pintype "bidirectional"))
      (node (ref "J3") (pin "1") (pinfunction "1_1") (pintype "passive"))
      (node (ref "J4") (pin "G1") (pinfunction "GND_1_G1") (pintype "bidirectional"))
      (node (ref "J4") (pin "G2") (pinfunction "GND_2_G2") (pintype "bidirectional"))
      (node (ref "J4") (pin "G3") (pinfunction "GND_3_G3") (pintype "bidirectional"))
      (node (ref "J4") (pin "G4") (pinfunction "GND_4_G4") (pintype "bidirectional"))
      (node (ref "J4") (pin "P6") (pinfunction "VSS_P6") (pintype "bidirectional"))
      (node (ref "MCP73831") (pin "2") (pinfunction "VSS_2") (pintype "power_in"))
      (node (ref "R1_PWRUSB") (pin "1") (pinfunction "1_1") (pintype "passive"))
      (node (ref "R2") (pin "1") (pinfunction "1_1") (pintype "passive"))
      (node (ref "R2-USB") (pin "2") (pinfunction "2_2") (pintype "passive"))
      (node (ref "R2-USB1") (pin "1") (pinfunction "1_1") (pintype "passive"))
      (node (ref "R2_BAT") (pin "1") (pinfunction "1_1") (pintype "passive"))
      (node (ref "R4") (pin "2") (pinfunction "2_2") (pintype "passive"))
      (node (ref "RESET_BUTTON") (pin "1") (pinfunction "1_1") (pintype "passive"))
      (node (ref "RESET_BUTTON") (pin "2") (pinfunction "2_2") (pintype "passive"))
      (node (ref "SENSOR2") (pin "1") (pinfunction "GND_1") (pintype "power_in"))
      (node (ref "SENSOR2") (pin "5") (pinfunction "SDO_5") (pintype "bidirectional"))
      (node (ref "SENSOR2") (pin "7") (pinfunction "GND_7") (pintype "power_in"))
      (node (ref "SJ1") (pin "1") (pinfunction "1_1") (pintype "passive"))
      (node (ref "TP4") (pin "TP") (pinfunction "TP_TP") (pintype "input"))
      (node (ref "TP5") (pin "TP") (pinfunction "TP_TP") (pintype "input"))
      (node (ref "U1") (pin "4") (pinfunction "GND_4") (pintype "power_in"))
      (node (ref "U1") (pin "9") (pinfunction "EXP_9") (pintype "passive"))
      (node (ref "U2") (pin "1") (pinfunction "GND_1") (pintype "power_in"))
      (node (ref "U2") (pin "28") (pinfunction "GND_28") (pintype "power_in"))
      (node (ref "U2") (pin "29_1") (pinfunction "GND_29_1") (pintype "power_in"))
      (node (ref "U2") (pin "29_2") (pinfunction "GND_29_2") (pintype "power_in"))
      (node (ref "U2") (pin "29_3") (pinfunction "GND_29_3") (pintype "power_in"))
      (node (ref "U2") (pin "29_4") (pinfunction "GND_29_4") (pintype "power_in"))
      (node (ref "U2") (pin "29_5") (pinfunction "GND_29_5") (pintype "power_in"))
      (node (ref "U2") (pin "29_6") (pinfunction "GND_29_6") (pintype "power_in"))
      (node (ref "U2") (pin "29_7") (pinfunction "GND_29_7") (pintype "power_in"))
      (node (ref "U2") (pin "29_8") (pinfunction "GND_29_8") (pintype "power_in"))
      (node (ref "U2") (pin "29_9") (pinfunction "GND_29_9") (pintype "power_in"))
      (node (ref "U3") (pin "13") (pinfunction "GND_13") (pintype "power_in"))
      (node (ref "U4") (pin "1") (pinfunction "CTG_1") (pintype "power_in"))
      (node (ref "U4") (pin "4") (pinfunction "GND_4") (pintype "power_in"))
      (node (ref "U4") (pin "6") (pinfunction "QSTRT_6") (pintype "input"))
      (node (ref "U4") (pin "9") (pinfunction "EP_9") (pintype "power_in"))
    )
    (net (code "14") (name "GPIO8") (class "Default")
      (node (ref "R1") (pin "2") (pinfunction "2_2") (pintype "passive"))
      (node (ref "U2") (pin "10") (pinfunction "IO8_10") (pintype "bidirectional"))
    )
    (net (code "15") (name "I2C_PW") (class "Default")
      (node (ref "C1") (pin "1") (pinfunction "1_1") (pintype "passive"))
      (node (ref "C2") (pin "1") (pinfunction "1_1") (pintype "passive"))
      (node (ref "R1-PINH") (pin "2") (pinfunction "2_2") (pintype "passive"))
      (node (ref "R2-PINH") (pin "2") (pinfunction "2_2") (pintype "passive"))
      (node (ref "SENSOR2") (pin "6") (pinfunction "VDDIO_6") (pintype "power_in"))
      (node (ref "U2") (pin "17") (pinfunction "IO19_17") (pintype "bidirectional"))
    )
    (net (code "16") (name "INT_RTC") (class "Default")
      (node (ref "R1-PINH1") (pin "1") (pinfunction "1_1") (pintype "passive"))
      (node (ref "TP15") (pin "TP") (pinfunction "TP_TP") (pintype "input"))
      (node (ref "U2") (pin "8") (pinfunction "IO0_8") (pintype "bidirectional"))
      (node (ref "U3") (pin "3") (pinfunction "SQW/~{INT}_3") (pintype "output"))
    )
    (net (code "17") (name "IO{slash}BOOT") (class "Default")
      (node (ref "BOOT_BUTTON") (pin "3") (pinfunction "3_3") (pintype "passive"))
      (node (ref "BOOT_BUTTON") (pin "4") (pinfunction "4_4") (pintype "passive"))
      (node (ref "C6") (pin "1") (pinfunction "1_1") (pintype "passive"))
      (node (ref "R_BOOT") (pin "1") (pinfunction "1_1") (pintype "passive"))
      (node (ref "U2") (pin "15") (pinfunction "IO9_15") (pintype "bidirectional"))
    )
    (net (code "18") (name "IO{slash}CHANGE") (class "Default")
      (node (ref "C10") (pin "1") (pinfunction "1_1") (pintype "passive"))
      (node (ref "CHANGE_BUTTON") (pin "3") (pinfunction "3_3") (pintype "passive"))
      (node (ref "CHANGE_BUTTON") (pin "4") (pinfunction "4_4") (pintype "passive"))
      (node (ref "R_CHANGE") (pin "1") (pinfunction "1_1") (pintype "passive"))
      (node (ref "U2") (pin "23") (pinfunction "IO15_23") (pintype "bidirectional"))
    )
    (net (code "19") (name "MISO") (class "Default")
      (node (ref "D12") (pin "2") (pinfunction "2_2") (pintype "passive"))
      (node (ref "J4") (pin "P7") (pinfunction "DAT0_P7") (pintype "bidirectional"))
      (node (ref "R8") (pin "1") (pinfunction "1_1") (pintype "passive"))
      (node (ref "TP6") (pin "TP") (pinfunction "TP_TP") (pintype "input"))
      (node (ref "U1") (pin "2") (pinfunction "DO(IO1)_2") (pintype "bidirectional"))
      (node (ref "U2") (pin "27") (pinfunction "IO2_27") (pintype "bidirectional"))
    )
    (net (code "20") (name "MOSI") (class "Default")
      (node (ref "D11") (pin "2") (pinfunction "2_2") (pintype "passive"))
      (node (ref "J1") (pin "14") (pinfunction "14_14") (pintype "bidirectional"))
      (node (ref "J4") (pin "P3") (pinfunction "CMD_P3") (pintype "bidirectional"))
      (node (ref "R7") (pin "1") (pinfunction "1_1") (pintype "passive"))
      (node (ref "TP7") (pin "TP") (pinfunction "TP_TP") (pintype "input"))
      (node (ref "U1") (pin "5") (pinfunction "DI(IO0)_5") (pintype "bidirectional"))
      (node (ref "U2") (pin "7") (pinfunction "IO7_7") (pintype "bidirectional"))
    )
    (net (code "21") (name "Net-(CHG_LED-PadC)") (class "Default")
      (node (ref "CHG_LED") (pin "C") (pinfunction "C_C") (pintype "passive"))
      (node (ref "R1_BAT") (pin "1") (pinfunction "1_1") (pintype "passive"))
    )
    (net (code "22") (name "Net-(D2-CATHODE)") (class "Default")
      (node (ref "C1_BAT1") (pin "1") (pinfunction "1_1") (pintype "passive"))
      (node (ref "D2") (pin "1") (pinfunction "CATHODE_1") (pintype "bidirectional"))
      (node (ref "IC4") (pin "1") (pinfunction "VIN_1") (pintype "bidirectional"))
      (node (ref "IC4") (pin "3") (pinfunction "CE_3") (pintype "bidirectional"))
      (node (ref "Q1") (pin "2") (pinfunction "S_2") (pintype "bidirectional"))
    )
    (net (code "23") (name "Net-(D3-A)") (class "Default")
      (node (ref "C4") (pin "1") (pinfunction "1_1") (pintype "passive"))
      (node (ref "D3") (pin "2") (pinfunction "A_2") (pintype "bidirectional"))
      (node (ref "D4") (pin "1") (pinfunction "K_1") (pintype "bidirectional"))
    )
    (net (code "24") (name "Net-(D7-CATHODE)") (class "Default")
      (node (ref "D7") (pin "1") (pinfunction "CATHODE_1") (pintype "bidirectional"))
      (node (ref "R_CAPACITOR") (pin "1") (pinfunction "1_1") (pintype "passive"))
    )
    (net (code "25") (name "Net-(EPD_C1-Pad2)") (class "Default")
      (node (ref "EPD_C1") (pin "2") (pinfunction "2_2") (pintype "passive"))
      (node (ref "J1") (pin "4") (pinfunction "4_4") (pintype "bidirectional"))
    )
    (net (code "26") (name "Net-(EPD_C2-Pad2)") (class "Default")
      (node (ref "EPD_C2") (pin "2") (pinfunction "2_2") (pintype "passive"))
      (node (ref "J1") (pin "5") (pinfunction "5_5") (pintype "bidirectional"))
    )
    (net (code "27") (name "Net-(EPD_C6-Pad2)") (class "Default")
      (node (ref "EPD_C6") (pin "2") (pinfunction "2_2") (pintype "passive"))
      (node (ref "J1") (pin "18") (pinfunction "18_18") (pintype "bidirectional"))
    )
    (net (code "28") (name "Net-(EPD_C7-Pad2)") (class "Default")
      (node (ref "EPD_C7") (pin "2") (pinfunction "2_2") (pintype "passive"))
      (node (ref "J1") (pin "19") (pinfunction "19_19") (pintype "bidirectional"))
    )
    (net (code "29") (name "Net-(EPD_C8-Pad2)") (class "Default")
      (node (ref "EPD_C8") (pin "2") (pinfunction "2_2") (pintype "passive"))
      (node (ref "J1") (pin "20") (pinfunction "20_20") (pintype "bidirectional"))
    )
    (net (code "30") (name "Net-(EPD_C10-Pad2)") (class "Default")
      (node (ref "EPD_C10") (pin "2") (pinfunction "2_2") (pintype "passive"))
      (node (ref "J1") (pin "22") (pinfunction "22_22") (pintype "bidirectional"))
    )
    (net (code "31") (name "Net-(EPD_C12-Pad2)") (class "Default")
      (node (ref "EPD_C12") (pin "2") (pinfunction "2_2") (pintype "passive"))
      (node (ref "J1") (pin "24") (pinfunction "24_24") (pintype "bidirectional"))
    )
    (net (code "32") (name "Net-(IC1-CT)") (class "Default")
      (node (ref "C_DELAY") (pin "1") (pinfunction "1_1") (pintype "passive"))
      (node (ref "IC1") (pin "5") (pinfunction "CT_5") (pintype "bidirectional"))
    )
    (net (code "33") (name "Net-(J2-PadA5)") (class "Default")
      (node (ref "J2") (pin "A5") (pinfunction "A5_A5") (pintype "bidirectional"))
      (node (ref "R2-USB1") (pin "2") (pinfunction "2_2") (pintype "passive"))
    )
    (net (code "34") (name "Net-(J2-PadB5)") (class "Default")
      (node (ref "J2") (pin "B5") (pinfunction "B5_B5") (pintype "bidirectional"))
      (node (ref "R2-USB") (pin "1") (pinfunction "1_1") (pintype "passive"))
    )
    (net (code "35") (name "Net-(MCP73831-PROG)") (class "Default")
      (node (ref "MCP73831") (pin "5") (pinfunction "PROG_5") (pintype "input"))
      (node (ref "R2_BAT") (pin "2") (pinfunction "2_2") (pintype "passive"))
    )
    (net (code "36") (name "Net-(MCP73831-STAT)") (class "Default")
      (node (ref "MCP73831") (pin "1") (pinfunction "STAT_1") (pintype "output"))
      (node (ref "R1_BAT") (pin "2") (pinfunction "2_2") (pintype "passive"))
    )
    (net (code "37") (name "Net-(SENSOR2-CSB)") (class "Default")
      (node (ref "SENSOR2") (pin "2") (pinfunction "CSB_2") (pintype "input"))
      (node (ref "SENSOR2") (pin "8") (pinfunction "VDD_8") (pintype "power_in"))
    )
    (net (code "38") (name "PREVGH") (class "Default")
      (node (ref "D5") (pin "1") (pinfunction "K_1") (pintype "bidirectional"))
      (node (ref "EPD_C9") (pin "2") (pinfunction "2_2") (pintype "passive"))
      (node (ref "J1") (pin "21") (pinfunction "21_21") (pintype "bidirectional"))
    )
    (net (code "39") (name "PREVGL") (class "Default")
      (node (ref "D4") (pin "2") (pinfunction "A_2") (pintype "bidirectional"))
      (node (ref "EPD_C11") (pin "2") (pinfunction "2_2") (pintype "passive"))
      (node (ref "J1") (pin "23") (pinfunction "23_23") (pintype "bidirectional"))
    )
    (net (code "40") (name "RESE") (class "Default")
      (node (ref "J1") (pin "3") (pinfunction "3_3") (pintype "bidirectional"))
      (node (ref "Q3") (pin "2") (pinfunction "S_2") (pintype "bidirectional"))
      (node (ref "R3") (pin "2") (pinfunction "2_2") (pintype "passive"))
    )
    (net (code "41") (name "RESE'") (class "Default")
      (node (ref "R2") (pin "2") (pinfunction "2_2") (pintype "passive"))
      (node (ref "R3") (pin "1") (pinfunction "1_1") (pintype "passive"))
      (node (ref "SJ1") (pin "2") (pinfunction "2_2") (pintype "passive"))
    )
    (net (code "42") (name "RESET") (class "Default")
      (node (ref "C5") (pin "1") (pinfunction "1_1") (pintype "passive"))
      (node (ref "IC1") (pin "1") (pinfunction "VOUT_1") (pintype "bidirectional"))
      (node (ref "RESET_BUTTON") (pin "3") (pinfunction "3_3") (pintype "passive"))
      (node (ref "RESET_BUTTON") (pin "4") (pinfunction "4_4") (pintype "passive"))
      (node (ref "R_RESET") (pin "1") (pinfunction "1_1") (pintype "passive"))
      (node (ref "U2") (pin "3") (pinfunction "EN_3") (pintype "input"))
    )
    (net (code "43") (name "RTC_RST") (class "Default")
      (node (ref "U2") (pin "16") (pinfunction "IO18_16") (pintype "bidirectional"))
      (node (ref "U3") (pin "4") (pinfunction "~{RST}_4") (pintype "input"))
    )
    (net (code "44") (name "RX") (class "Default")
      (node (ref "TP2") (pin "TP") (pinfunction "TP_TP") (pintype "input"))
      (node (ref "U2") (pin "24") (pinfunction "RXD0/GPIO17_24") (pintype "bidirectional"))
    )
    (net (code "45") (name "SCK") (class "Default")
      (node (ref "D10") (pin "2") (pinfunction "2_2") (pintype "passive"))
      (node (ref "J1") (pin "13") (pinfunction "13_13") (pintype "bidirectional"))
      (node (ref "J4") (pin "P5") (pinfunction "CLK_P5") (pintype "bidirectional"))
      (node (ref "R6") (pin "1") (pinfunction "1_1") (pintype "passive"))
      (node (ref "TP8") (pin "TP") (pinfunction "TP_TP") (pintype "input"))
      (node (ref "U1") (pin "6") (pinfunction "CLK_6") (pintype "input"))
      (node (ref "U2") (pin "6") (pinfunction "IO6_6") (pintype "bidirectional"))
    )
    (net (code "46") (name "SCL") (class "Default")
      (node (ref "J3") (pin "4") (pinfunction "4_4") (pintype "power_in"))
      (node (ref "R2-PINH") (pin "1") (pinfunction "1_1") (pintype "passive"))
      (node (ref "SENSOR2") (pin "4") (pinfunction "SCK_4") (pintype "input"))
      (node (ref "U2") (pin "20") (pinfunction "IO22_20") (pintype "bidirectional"))
      (node (ref "U3") (pin "16") (pinfunction "SCL_16") (pintype "input"))
      (node (ref "U4") (pin "7") (pinfunction "SCL_7") (pintype "input"))
    )
    (net (code "47") (name "SDA") (class "Default")
      (node (ref "J3") (pin "3") (pinfunction "3_3") (pintype "power_in"))
      (node (ref "R1-PINH") (pin "1") (pinfunction "1_1") (pintype "passive"))
      (node (ref "SENSOR2") (pin "3") (pinfunction "SDI_3") (pintype "bidirectional"))
      (node (ref "U2") (pin "19") (pinfunction "IO21_19") (pintype "bidirectional"))
      (node (ref "U3") (pin "15") (pinfunction "SDA_15") (pintype "bidirectional"))
      (node (ref "U4") (pin "8") (pinfunction "SDA_8") (pintype "bidirectional"))
    )
    (net (code "48") (name "SRC") (class "Default")
      (node (ref "C4") (pin "2") (pinfunction "2_2") (pintype "passive"))
      (node (ref "D5") (pin "2") (pinfunction "A_2") (pintype "bidirectional"))
      (node (ref "L1") (pin "1") (pinfunction "1_1") (pintype "passive"))
      (node (ref "Q3") (pin "3") (pinfunction "D_3") (pintype "bidirectional"))
    )
    (net (code "49") (name "SS_SD") (class "Default")
      (node (ref "D8") (pin "2") (pinfunction "2_2") (pintype "passive"))
      (node (ref "J4") (pin "P2") (pinfunction "CD/DAT3_P2") (pintype "bidirectional"))
      (node (ref "R10") (pin "1") (pinfunction "1_1") (pintype "passive"))
      (node (ref "U2") (pin "4") (pinfunction "IO4_4") (pintype "bidirectional"))
    )
    (net (code "50") (name "TX") (class "Default")
      (node (ref "TP1") (pin "TP") (pinfunction "TP_TP") (pintype "input"))
      (node (ref "U2") (pin "25") (pinfunction "TXD0/GPIO16_25") (pintype "bidirectional"))
    )
    (net (code "51") (name "USB_D+") (class "Default")
      (node (ref "D1") (pin "1") (pinfunction "I/O1_1_1") (pintype "bidirectional"))
      (node (ref "U2") (pin "14") (pinfunction "IO13_14") (pintype "bidirectional"))
    )
    (net (code "52") (name "USB_D-") (class "Default")
      (node (ref "D1") (pin "3") (pinfunction "I/O2_1_3") (pintype "bidirectional"))
      (node (ref "U2") (pin "13") (pinfunction "IO12_13") (pintype "bidirectional"))
    )
    (net (code "53") (name "VBAT") (class "Default")
      (node (ref "C2_BAT") (pin "1") (pinfunction "1_1") (pintype "passive"))
      (node (ref "MCP73831") (pin "3") (pinfunction "VBAT_3") (pintype "power_in"))
      (node (ref "Q1") (pin "3") (pinfunction "D_3") (pintype "bidirectional"))
      (node (ref "TP3") (pin "TP") (pinfunction "TP_TP") (pintype "input"))
      (node (ref "U4") (pin "2") (pinfunction "CELL_2") (pintype "power_in"))
      (node (ref "U4") (pin "3") (pinfunction "VDD_3") (pintype "power_in"))
    )
    (net (code "54") (name "VBUS") (class "Default")
      (node (ref "C1_BAT") (pin "1") (pinfunction "1_1") (pintype "passive"))
      (node (ref "C4_USB") (pin "1") (pinfunction "1_1") (pintype "passive"))
      (node (ref "C5_USB") (pin "1") (pinfunction "1_1") (pintype "passive"))
      (node (ref "CHG_LED") (pin "A") (pinfunction "A_A") (pintype "passive"))
      (node (ref "D1") (pin "5") (pinfunction "VBUS_5") (pintype "bidirectional"))
      (node (ref "D2") (pin "2") (pinfunction "ANODE_2") (pintype "bidirectional"))
      (node (ref "MCP73831") (pin "4") (pinfunction "VIN_4") (pintype "power_in"))
      (node (ref "PFMF.050.1") (pin "2") (pinfunction "2_2") (pintype "passive"))
      (node (ref "Q1") (pin "1") (pinfunction "G_1") (pintype "bidirectional"))
      (node (ref "R1_PWRUSB") (pin "2") (pinfunction "2_2") (pintype "passive"))
      (node (ref "TP14") (pin "TP") (pinfunction "TP_TP") (pintype "input"))
    )
    (net (code "55") (name "VRTC") (class "Default")
      (node (ref "C10_SUPERCAP") (pin "2") (pinfunction "2_2") (pintype "passive"))
      (node (ref "C8") (pin "1") (pinfunction "1_1") (pintype "passive"))
      (node (ref "R_CAPACITOR") (pin "2") (pinfunction "2_2") (pintype "passive"))
      (node (ref "U3") (pin "14") (pinfunction "VBAT_14") (pintype "power_in"))
    )
    (net (code "56") (name "VUSB") (class "Default")
      (node (ref "J2") (pin "A4") (pinfunction "A4_A4") (pintype "bidirectional"))
      (node (ref "J2") (pin "A9") (pinfunction "A9_A9") (pintype "bidirectional"))
      (node (ref "J2") (pin "B4") (pinfunction "B4_B4") (pintype "bidirectional"))
      (node (ref "J2") (pin "B9") (pinfunction "B9_B9") (pintype "bidirectional"))
      (node (ref "PFMF.050.1") (pin "1") (pinfunction "1_1") (pintype "passive"))
    )
    (net (code "57") (name "unconnected-(IC1-NC-Pad4)") (class "Default")
      (node (ref "IC1") (pin "4") (pinfunction "NC_4") (pintype "no_connect"))
    )
    (net (code "58") (name "unconnected-(IC4-NC-Pad4)") (class "Default")
      (node (ref "IC4") (pin "4") (pinfunction "NC_4") (pintype "no_connect"))
    )
    (net (code "59") (name "unconnected-(J1-Pad1)") (class "Default")
      (node (ref "J1") (pin "1") (pinfunction "1_1") (pintype "bidirectional"))
    )
    (net (code "60") (name "unconnected-(J1-Pad6)") (class "Default")
      (node (ref "J1") (pin "6") (pinfunction "6_6") (pintype "bidirectional"))
    )
    (net (code "61") (name "unconnected-(J1-Pad7)") (class "Default")
      (node (ref "J1") (pin "7") (pinfunction "7_7") (pintype "bidirectional"))
    )
    (net (code "62") (name "unconnected-(J2-PadA8)") (class "Default")
      (node (ref "J2") (pin "A8") (pinfunction "A8_A8") (pintype "bidirectional"))
    )
    (net (code "63") (name "unconnected-(J2-PadB8)") (class "Default")
      (node (ref "J2") (pin "B8") (pinfunction "B8_B8") (pintype "bidirectional"))
    )
    (net (code "64") (name "unconnected-(J4-DAT1-PadP8)") (class "Default")
      (node (ref "J4") (pin "P8") (pinfunction "DAT1_P8") (pintype "bidirectional"))
    )
    (net (code "65") (name "unconnected-(J4-DAT2-PadP1)") (class "Default")
      (node (ref "J4") (pin "P1") (pinfunction "DAT2_P1") (pintype "bidirectional"))
    )
    (net (code "66") (name "unconnected-(J4-DETECTION_1-PadS1)") (class "Default")
      (node (ref "J4") (pin "S1") (pinfunction "DETECTION_1_S1") (pintype "bidirectional"))
    )
    (net (code "67") (name "unconnected-(J4-DETECTION_2-PadS2)") (class "Default")
      (node (ref "J4") (pin "S2") (pinfunction "DETECTION_2_S2") (pintype "bidirectional"))
    )
    (net (code "68") (name "unconnected-(U2-NC-Pad22)") (class "Default")
      (node (ref "U2") (pin "22") (pinfunction "NC_22") (pintype "no_connect"))
    )
    (net (code "69") (name "unconnected-(U4-~{ALERT}-Pad5)") (class "Default")
      (node (ref "U4") (pin "5") (pinfunction "~{ALERT}_5") (pintype "output"))
    )
  )
)
